# hud.net
KiCad netlist of a schematic drawn in EAGLE
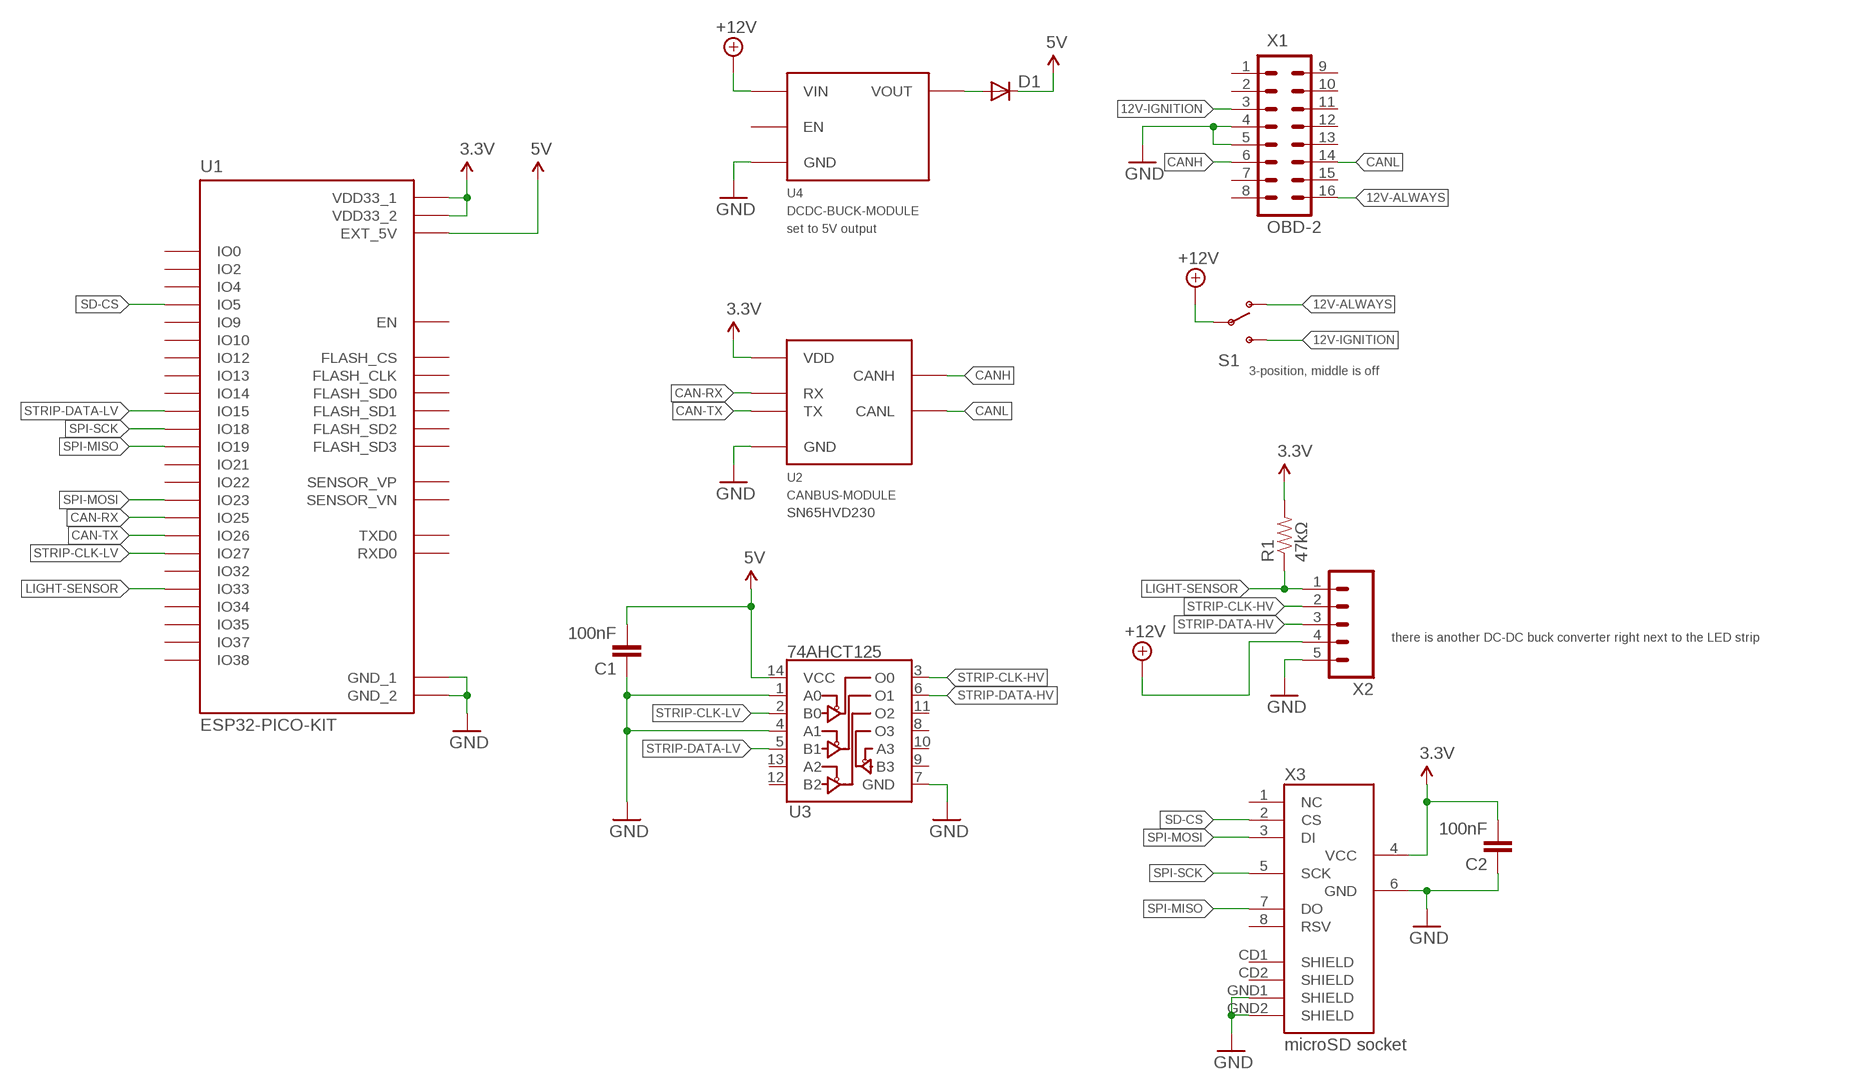
[diagram p0: schematic, sheet 1]

(export (version "E")
  (design (tool "Eeschema 10.0.6"))
  (components
    (comp (ref "C1")
      (value "100nF")
      (footprint "eagle-import:0402-CAP")
      (libsource (lib "eagle-import") (part "CAP0402-CAP"))
    )
    (comp (ref "C2")
      (value "100nF")
      (footprint "eagle-import:0402-CAP")
      (libsource (lib "eagle-import") (part "CAP0402-CAP"))
    )
    (comp (ref "D1")
      (value "DIODE1N4148")
      (footprint "eagle-import:DIODE-1N4148")
      (libsource (lib "eagle-import") (part "DIODE1N4148"))
    )
    (comp (ref "R1")
      (value "47kΩ")
      (footprint "eagle-import:0805")
      (libsource (lib "eagle-import") (part "RESISTOR0805-RES"))
    )
    (comp (ref "S1")
      (value "SWITCH-SPSTPTH")
      (footprint "eagle-import:SWITCH-SPDT")
      (libsource (lib "eagle-import") (part "SWITCH-SPSTPTH"))
    )
    (comp (ref "U1")
      (value "ESP32-PICO-KIT")
      (footprint "eagle-import:XCVR_ESP32-PICO-KIT")
      (fields (field (name "MF") "Espressif Systems"))
      (libsource (lib "eagle-import") (part "ESP32-PICO-KIT"))
    )
    (comp (ref "U3")
      (value "74AHCT125")
      (footprint "eagle-import:SO014")
      (libsource (lib "eagle-import") (part "74ACT125D"))
    )
    (comp (ref "X1")
      (value "OBD-2")
      (footprint "eagle-import:2X8")
      (libsource (lib "eagle-import") (part "M08X2"))
    )
    (comp (ref "X2")
      (value "M05PTH")
      (footprint "eagle-import:1X05")
      (libsource (lib "eagle-import") (part "M05PTH"))
    )
    (comp (ref "X3")
      (value "microSD socket")
      (footprint "eagle-import:USD-SOCKET-PP")
      (libsource (lib "eagle-import") (part "USD-SOCKETUSD"))
    )
  )
  (nets
    (net (code "1") (name "+12V") (class "Default")
      (node (ref "S1") (pin "2") (pinfunction "P_2") (pintype "passive"))
      (node (ref "X2") (pin "4") (pinfunction "4_4") (pintype "passive"))
    )
    (net (code "3") (name "3.3V") (class "Default")
      (node (ref "C2") (pin "2") (pinfunction "2_2") (pintype "passive"))
      (node (ref "R1") (pin "2") (pinfunction "2_2") (pintype "passive"))
      (node (ref "U1") (pin "J2_20") (pinfunction "VDD33_1_J2_20") (pintype "power_in"))
      (node (ref "U1") (pin "J3_18") (pinfunction "VDD33_2_J3_18") (pintype "power_in"))
      (node (ref "X3") (pin "4") (pinfunction "VCC_4") (pintype "bidirectional"))
    )
    (net (code "4") (name "5V") (class "Default")
      (node (ref "C1") (pin "2") (pinfunction "2_2") (pintype "passive"))
      (node (ref "D1") (pin "C") (pinfunction "C_C") (pintype "passive"))
      (node (ref "U1") (pin "J3_20") (pinfunction "EXT_5V_J3_20") (pintype "power_in"))
      (node (ref "U3") (pin "14") (pinfunction "VCC_14") (pintype "bidirectional"))
    )
    (net (code "5") (name "12V-ALWAYS") (class "Default")
      (node (ref "S1") (pin "1") (pinfunction "O_1") (pintype "passive"))
      (node (ref "X1") (pin "16") (pinfunction "16_16") (pintype "passive"))
    )
    (net (code "6") (name "12V-IGNITION") (class "Default")
      (node (ref "S1") (pin "3") (pinfunction "S_3") (pintype "passive"))
      (node (ref "X1") (pin "3") (pinfunction "3_3") (pintype "passive"))
    )
    (net (code "7") (name "CAN-RX") (class "Default")
      (node (ref "U1") (pin "J3_6") (pinfunction "IO25_J3_6") (pintype "bidirectional"))
    )
    (net (code "8") (name "CAN-TX") (class "Default")
      (node (ref "U1") (pin "J3_7") (pinfunction "IO26_J3_7") (pintype "bidirectional"))
    )
    (net (code "9") (name "CANH") (class "Default")
      (node (ref "X1") (pin "6") (pinfunction "6_6") (pintype "passive"))
    )
    (net (code "10") (name "CANL") (class "Default")
      (node (ref "X1") (pin "14") (pinfunction "14_14") (pintype "passive"))
    )
    (net (code "11") (name "GND") (class "Default")
      (node (ref "C1") (pin "1") (pinfunction "1_1") (pintype "passive"))
      (node (ref "C2") (pin "1") (pinfunction "1_1") (pintype "passive"))
      (node (ref "U1") (pin "J2_19") (pinfunction "GND_1_J2_19") (pintype "power_in"))
      (node (ref "U1") (pin "J3_19") (pinfunction "GND_2_J3_19") (pintype "power_in"))
      (node (ref "U3") (pin "1") (pinfunction "A0_1") (pintype "bidirectional"))
      (node (ref "U3") (pin "4") (pinfunction "A1_4") (pintype "bidirectional"))
      (node (ref "U3") (pin "7") (pinfunction "GND_7") (pintype "bidirectional"))
      (node (ref "X1") (pin "4") (pinfunction "4_4") (pintype "passive"))
      (node (ref "X1") (pin "5") (pinfunction "5_5") (pintype "passive"))
      (node (ref "X2") (pin "5") (pinfunction "5_5") (pintype "passive"))
      (node (ref "X3") (pin "6") (pinfunction "GND_6") (pintype "bidirectional"))
      (node (ref "X3") (pin "GND1") (pinfunction "SHIELD_GND1") (pintype "bidirectional"))
      (node (ref "X3") (pin "GND2") (pinfunction "SHIELD_GND2") (pintype "bidirectional"))
    )
    (net (code "12") (name "LIGHT-SENSOR") (class "Default")
      (node (ref "R1") (pin "1") (pinfunction "1_1") (pintype "passive"))
      (node (ref "U1") (pin "J3_9") (pinfunction "IO33_J3_9") (pintype "bidirectional"))
      (node (ref "X2") (pin "1") (pinfunction "1_1") (pintype "passive"))
    )
    (net (code "13") (name "Net-(D1-PadA)") (class "Default")
      (node (ref "D1") (pin "A") (pinfunction "A_A") (pintype "passive"))
    )
    (net (code "14") (name "SD-CS") (class "Default")
      (node (ref "U1") (pin "J2_9") (pinfunction "IO5_J2_9") (pintype "bidirectional"))
      (node (ref "X3") (pin "2") (pinfunction "CS_2") (pintype "bidirectional"))
    )
    (net (code "15") (name "SPI-MISO") (class "Default")
      (node (ref "U1") (pin "J2_6") (pinfunction "IO19_J2_6") (pintype "bidirectional"))
      (node (ref "X3") (pin "7") (pinfunction "DO_7") (pintype "bidirectional"))
    )
    (net (code "16") (name "SPI-MOSI") (class "Default")
      (node (ref "U1") (pin "J2_7") (pinfunction "IO23_J2_7") (pintype "bidirectional"))
      (node (ref "X3") (pin "3") (pinfunction "DI_3") (pintype "bidirectional"))
    )
    (net (code "17") (name "SPI-SCK") (class "Default")
      (node (ref "U1") (pin "J2_8") (pinfunction "IO18_J2_8") (pintype "bidirectional"))
      (node (ref "X3") (pin "5") (pinfunction "SCK_5") (pintype "bidirectional"))
    )
    (net (code "18") (name "STRIP-CLK-HV") (class "Default")
      (node (ref "U3") (pin "3") (pinfunction "O0_3") (pintype "bidirectional"))
      (node (ref "X2") (pin "2") (pinfunction "2_2") (pintype "passive"))
    )
    (net (code "19") (name "STRIP-CLK-LV") (class "Default")
      (node (ref "U1") (pin "J3_10") (pinfunction "IO27_J3_10") (pintype "bidirectional"))
      (node (ref "U3") (pin "2") (pinfunction "B0_2") (pintype "bidirectional"))
    )
    (net (code "20") (name "STRIP-DATA-HV") (class "Default")
      (node (ref "U3") (pin "6") (pinfunction "O1_6") (pintype "bidirectional"))
      (node (ref "X2") (pin "3") (pinfunction "3_3") (pintype "passive"))
    )
    (net (code "21") (name "STRIP-DATA-LV") (class "Default")
      (node (ref "U1") (pin "J3_14") (pinfunction "IO15_J3_14") (pintype "bidirectional"))
      (node (ref "U3") (pin "5") (pinfunction "B1_5") (pintype "bidirectional"))
    )
    (net (code "22") (name "unconnected-(U1-EN-PadJ2_18)") (class "Default")
      (node (ref "U1") (pin "J2_18") (pinfunction "EN_J2_18") (pintype "input"))
    )
    (net (code "23") (name "unconnected-(U1-FLASH_CLK-PadJ2_3)") (class "Default")
      (node (ref "U1") (pin "J2_3") (pinfunction "FLASH_CLK_J2_3") (pintype "bidirectional"))
    )
    (net (code "24") (name "unconnected-(U1-FLASH_CS-PadJ3_1)") (class "Default")
      (node (ref "U1") (pin "J3_1") (pinfunction "FLASH_CS_J3_1") (pintype "bidirectional"))
    )
    (net (code "25") (name "unconnected-(U1-FLASH_SD0-PadJ3_2)") (class "Default")
      (node (ref "U1") (pin "J3_2") (pinfunction "FLASH_SD0_J3_2") (pintype "bidirectional"))
    )
    (net (code "26") (name "unconnected-(U1-FLASH_SD1-PadJ2_1)") (class "Default")
      (node (ref "U1") (pin "J2_1") (pinfunction "FLASH_SD1_J2_1") (pintype "bidirectional"))
    )
    (net (code "27") (name "unconnected-(U1-FLASH_SD2-PadJ3_3)") (class "Default")
      (node (ref "U1") (pin "J3_3") (pinfunction "FLASH_SD2_J3_3") (pintype "bidirectional"))
    )
    (net (code "28") (name "unconnected-(U1-FLASH_SD3-PadJ2_2)") (class "Default")
      (node (ref "U1") (pin "J2_2") (pinfunction "FLASH_SD3_J2_2") (pintype "bidirectional"))
    )
    (net (code "29") (name "unconnected-(U1-IO0-PadJ3_17)") (class "Default")
      (node (ref "U1") (pin "J3_17") (pinfunction "IO0_J3_17") (pintype "bidirectional"))
    )
    (net (code "30") (name "unconnected-(U1-IO2-PadJ3_15)") (class "Default")
      (node (ref "U1") (pin "J3_15") (pinfunction "IO2_J3_15") (pintype "bidirectional"))
    )
    (net (code "31") (name "unconnected-(U1-IO4-PadJ3_16)") (class "Default")
      (node (ref "U1") (pin "J3_16") (pinfunction "IO4_J3_16") (pintype "bidirectional"))
    )
    (net (code "32") (name "unconnected-(U1-IO9-PadJ2_11)") (class "Default")
      (node (ref "U1") (pin "J2_11") (pinfunction "IO9_J2_11") (pintype "bidirectional"))
    )
    (net (code "33") (name "unconnected-(U1-IO10-PadJ2_10)") (class "Default")
      (node (ref "U1") (pin "J2_10") (pinfunction "IO10_J2_10") (pintype "bidirectional"))
    )
    (net (code "34") (name "unconnected-(U1-IO12-PadJ3_12)") (class "Default")
      (node (ref "U1") (pin "J3_12") (pinfunction "IO12_J3_12") (pintype "bidirectional"))
    )
    (net (code "35") (name "unconnected-(U1-IO13-PadJ3_13)") (class "Default")
      (node (ref "U1") (pin "J3_13") (pinfunction "IO13_J3_13") (pintype "bidirectional"))
    )
    (net (code "36") (name "unconnected-(U1-IO14-PadJ3_11)") (class "Default")
      (node (ref "U1") (pin "J3_11") (pinfunction "IO14_J3_11") (pintype "bidirectional"))
    )
    (net (code "37") (name "unconnected-(U1-IO21-PadJ2_4)") (class "Default")
      (node (ref "U1") (pin "J2_4") (pinfunction "IO21_J2_4") (pintype "bidirectional"))
    )
    (net (code "38") (name "unconnected-(U1-IO22-PadJ2_5)") (class "Default")
      (node (ref "U1") (pin "J2_5") (pinfunction "IO22_J2_5") (pintype "bidirectional"))
    )
    (net (code "39") (name "unconnected-(U1-IO32-PadJ3_8)") (class "Default")
      (node (ref "U1") (pin "J3_8") (pinfunction "IO32_J3_8") (pintype "bidirectional"))
    )
    (net (code "40") (name "unconnected-(U1-IO34-PadJ2_15)") (class "Default")
      (node (ref "U1") (pin "J2_15") (pinfunction "IO34_J2_15") (pintype "input"))
    )
    (net (code "41") (name "unconnected-(U1-IO35-PadJ2_14)") (class "Default")
      (node (ref "U1") (pin "J2_14") (pinfunction "IO35_J2_14") (pintype "input"))
    )
    (net (code "42") (name "unconnected-(U1-IO37-PadJ2_17)") (class "Default")
      (node (ref "U1") (pin "J2_17") (pinfunction "IO37_J2_17") (pintype "input"))
    )
    (net (code "43") (name "unconnected-(U1-IO38-PadJ2_16)") (class "Default")
      (node (ref "U1") (pin "J2_16") (pinfunction "IO38_J2_16") (pintype "input"))
    )
    (net (code "44") (name "unconnected-(U1-RXD0-PadJ2_12)") (class "Default")
      (node (ref "U1") (pin "J2_12") (pinfunction "RXD0_J2_12") (pintype "bidirectional"))
    )
    (net (code "45") (name "unconnected-(U1-SENSOR_VN-PadJ3_5)") (class "Default")
      (node (ref "U1") (pin "J3_5") (pinfunction "SENSOR_VN_J3_5") (pintype "input"))
    )
    (net (code "46") (name "unconnected-(U1-SENSOR_VP-PadJ3_4)") (class "Default")
      (node (ref "U1") (pin "J3_4") (pinfunction "SENSOR_VP_J3_4") (pintype "input"))
    )
    (net (code "47") (name "unconnected-(U1-TXD0-PadJ2_13)") (class "Default")
      (node (ref "U1") (pin "J2_13") (pinfunction "TXD0_J2_13") (pintype "bidirectional"))
    )
    (net (code "48") (name "unconnected-(U3-A2-Pad13)") (class "Default")
      (node (ref "U3") (pin "13") (pinfunction "A2_13") (pintype "bidirectional"))
    )
    (net (code "49") (name "unconnected-(U3-A3-Pad10)") (class "Default")
      (node (ref "U3") (pin "10") (pinfunction "A3_10") (pintype "bidirectional"))
    )
    (net (code "50") (name "unconnected-(U3-B2-Pad12)") (class "Default")
      (node (ref "U3") (pin "12") (pinfunction "B2_12") (pintype "bidirectional"))
    )
    (net (code "51") (name "unconnected-(U3-B3-Pad9)") (class "Default")
      (node (ref "U3") (pin "9") (pinfunction "B3_9") (pintype "bidirectional"))
    )
    (net (code "52") (name "unconnected-(U3-O2-Pad11)") (class "Default")
      (node (ref "U3") (pin "11") (pinfunction "O2_11") (pintype "bidirectional"))
    )
    (net (code "53") (name "unconnected-(U3-O3-Pad8)") (class "Default")
      (node (ref "U3") (pin "8") (pinfunction "O3_8") (pintype "bidirectional"))
    )
    (net (code "54") (name "unconnected-(X1-Pad1)") (class "Default")
      (node (ref "X1") (pin "1") (pinfunction "1_1") (pintype "passive"))
    )
    (net (code "55") (name "unconnected-(X1-Pad2)") (class "Default")
      (node (ref "X1") (pin "2") (pinfunction "2_2") (pintype "passive"))
    )
    (net (code "56") (name "unconnected-(X1-Pad7)") (class "Default")
      (node (ref "X1") (pin "7") (pinfunction "7_7") (pintype "passive"))
    )
    (net (code "57") (name "unconnected-(X1-Pad8)") (class "Default")
      (node (ref "X1") (pin "8") (pinfunction "8_8") (pintype "passive"))
    )
    (net (code "58") (name "unconnected-(X1-Pad9)") (class "Default")
      (node (ref "X1") (pin "9") (pinfunction "9_9") (pintype "passive"))
    )
    (net (code "59") (name "unconnected-(X1-Pad10)") (class "Default")
      (node (ref "X1") (pin "10") (pinfunction "10_10") (pintype "passive"))
    )
    (net (code "60") (name "unconnected-(X1-Pad11)") (class "Default")
      (node (ref "X1") (pin "11") (pinfunction "11_11") (pintype "passive"))
    )
    (net (code "61") (name "unconnected-(X1-Pad12)") (class "Default")
      (node (ref "X1") (pin "12") (pinfunction "12_12") (pintype "passive"))
    )
    (net (code "62") (name "unconnected-(X1-Pad13)") (class "Default")
      (node (ref "X1") (pin "13") (pinfunction "13_13") (pintype "passive"))
    )
    (net (code "63") (name "unconnected-(X1-Pad15)") (class "Default")
      (node (ref "X1") (pin "15") (pinfunction "15_15") (pintype "passive"))
    )
    (net (code "64") (name "unconnected-(X3-NC-Pad1)") (class "Default")
      (node (ref "X3") (pin "1") (pinfunction "NC_1") (pintype "bidirectional"))
    )
    (net (code "65") (name "unconnected-(X3-RSV-Pad8)") (class "Default")
      (node (ref "X3") (pin "8") (pinfunction "RSV_8") (pintype "bidirectional"))
    )
    (net (code "66") (name "unconnected-(X3-SHIELD-PadCD1)") (class "Default")
      (node (ref "X3") (pin "CD1") (pinfunction "SHIELD_CD1") (pintype "bidirectional"))
    )
    (net (code "67") (name "unconnected-(X3-SHIELD-PadCD2)") (class "Default")
      (node (ref "X3") (pin "CD2") (pinfunction "SHIELD_CD2") (pintype "bidirectional"))
    )
  )
)
